# SD_Card_Multiplexer.net
KiCad netlist of a schematic drawn in Altium Designer
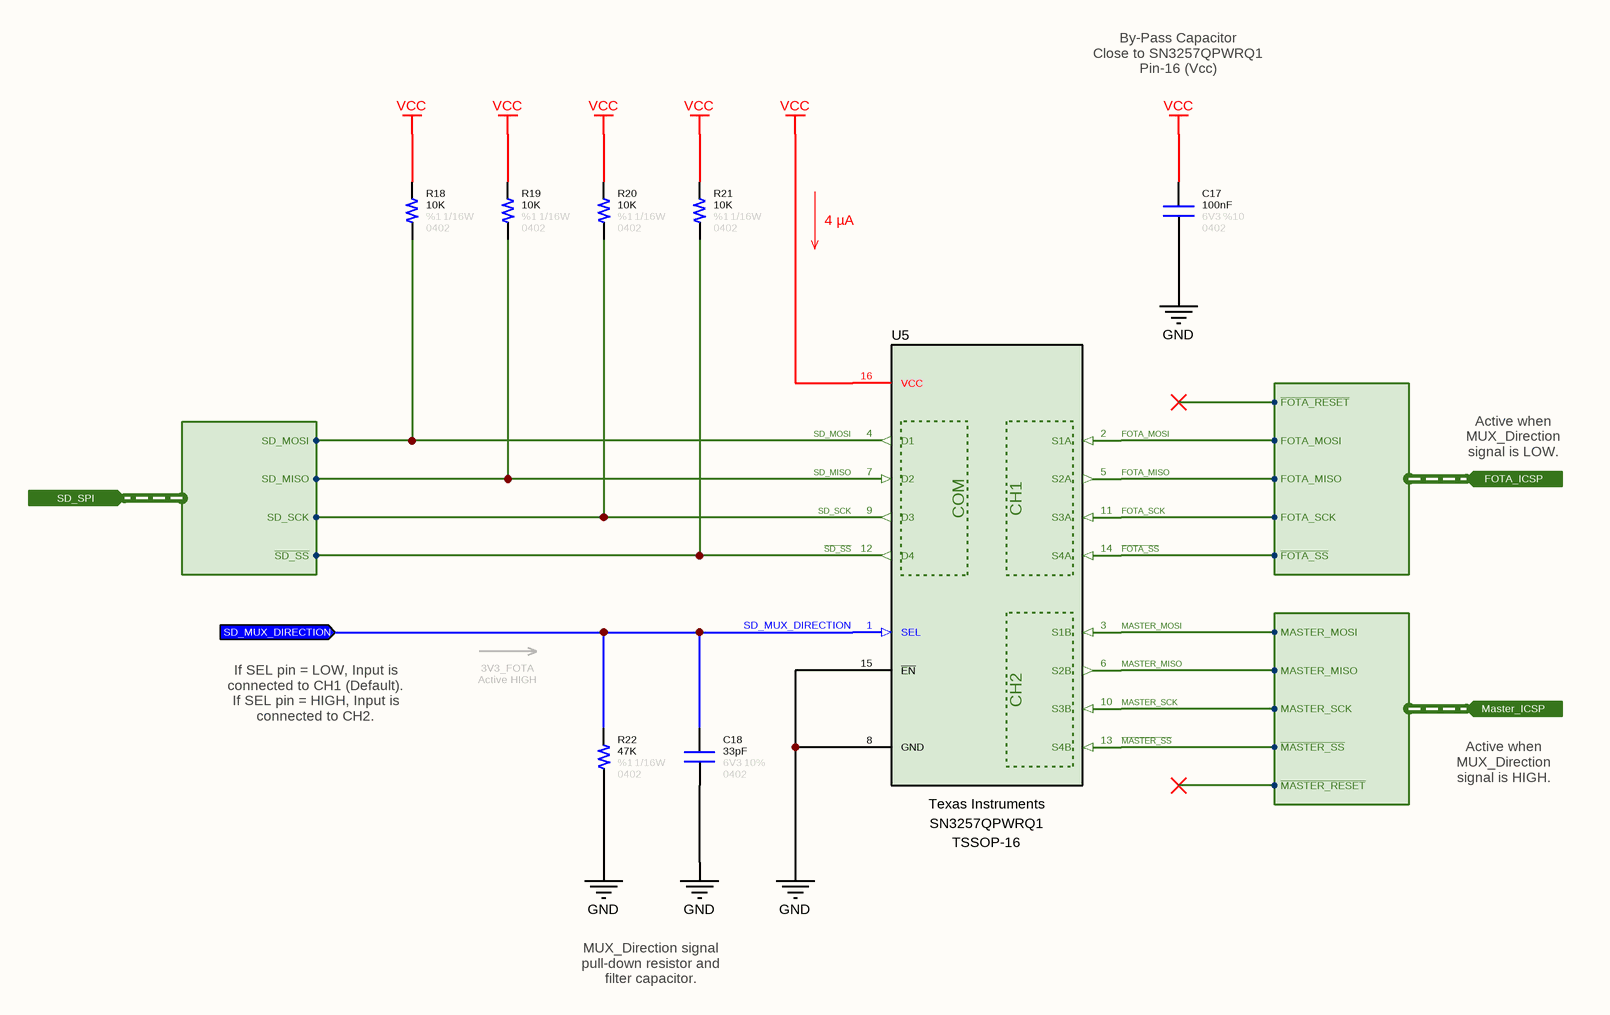
[diagram p0: SD Card Multiplexer.SchDoc]

(export (version "E")
  (design (tool "Eeschema 10.0.6"))
  (components
    (comp (ref "C17")
      (value "100nF")
      (footprint "CAPACITOR_0402")
      (description "Capacitor - 100nF [0402-6V3] (Ceramic)")
      (fields
        (field (name "MANUFACTURER PART NUMBER") "04026D104KAT4A")
        (field (name "TOLERANCE") "%10")
        (field (name "VOLTAGE") "6V3")
        (field (name "CASE") "0402")
        (field (name "Comment") "Capacitor - 100nF [0402] (Ceramic)")
      )
      (libsource (lib "P101DA_Library") (part "Capacitor - 100nF [0402-6V3]"))
    )
    (comp (ref "C18")
      (value "33pF")
      (footprint "CAPACITOR_0402")
      (description "Capacitor - 33pF [0402] (Ceramic)")
      (fields
        (field (name "MANUFACTURER PART NUMBER") "C0402C330J9RACAUTO")
        (field (name "TOLERANCE") "10%")
        (field (name "CASE") "0402")
        (field (name "VOLTAGE") "6V3")
      )
      (libsource (lib "P101DA_Library") (part "Capacitor - 33pF [0402-6V3]"))
    )
    (comp (ref "R18")
      (value "10K")
      (footprint "RESISTOR_0402")
      (description "Thick Film Resistors - SMD 1/16 W 10 KOhm 1%")
      (fields
        (field (name "MANUFACTURER PART NUMBER") "CRCW040210K0FKED")
        (field (name "TOLERANCE") "%1")
        (field (name "CASE") "0402")
        (field (name "POWER") "1/16W")
        (field (name "Comment") "10K - 0402 - %1 - 1/16W")
      )
      (libsource (lib "P101DA_Library") (part "Resistor - 10K [0402]"))
    )
    (comp (ref "R19")
      (value "10K")
      (footprint "RESISTOR_0402")
      (description "Thick Film Resistors - SMD 1/16 W 10 KOhm 1%")
      (fields
        (field (name "MANUFACTURER PART NUMBER") "CRCW040210K0FKED")
        (field (name "TOLERANCE") "%1")
        (field (name "CASE") "0402")
        (field (name "POWER") "1/16W")
        (field (name "Comment") "10K - 0402 - %1 - 1/16W")
      )
      (libsource (lib "P101DA_Library") (part "Resistor - 10K [0402]"))
    )
    (comp (ref "R20")
      (value "10K")
      (footprint "RESISTOR_0402")
      (description "Thick Film Resistors - SMD 1/16 W 10 KOhm 1%")
      (fields
        (field (name "MANUFACTURER PART NUMBER") "CRCW040210K0FKED")
        (field (name "TOLERANCE") "%1")
        (field (name "CASE") "0402")
        (field (name "POWER") "1/16W")
        (field (name "Comment") "10K - 0402 - %1 - 1/16W")
      )
      (libsource (lib "P101DA_Library") (part "Resistor - 10K [0402]"))
    )
    (comp (ref "R21")
      (value "10K")
      (footprint "RESISTOR_0402")
      (description "Thick Film Resistors - SMD 1/16 W 10 KOhm 1%")
      (fields
        (field (name "MANUFACTURER PART NUMBER") "CRCW040210K0FKED")
        (field (name "TOLERANCE") "%1")
        (field (name "CASE") "0402")
        (field (name "POWER") "1/16W")
        (field (name "Comment") "10K - 0402 - %1 - 1/16W")
      )
      (libsource (lib "P101DA_Library") (part "Resistor - 10K [0402]"))
    )
    (comp (ref "R22")
      (value "47K")
      (footprint "RESISTOR_0402")
      (description "Thick Film Resistors - SMD 1/16 W 47 KOhm 1%")
      (fields
        (field (name "MANUFACTURER PART NUMBER") "CRCW040247K0FKED")
        (field (name "TOLERANCE") "%1")
        (field (name "CASE") "0402")
        (field (name "POWER") "1/16W")
        (field (name "Comment") "47K - 0402 - %1 - 1/16W")
      )
      (libsource (lib "P101DA_Library") (part "Resistor - 47K [0402]"))
    )
    (comp (ref "U5")
      (value "SN3257QPWRQ1")
      (footprint "TSSOP-16")
      (fields
        (field (name "MANUFACTURER NAME") "Texas Instruments")
        (field (name "MANUFACTURER PART NUMBER") "SN3257QPWRQ1")
        (field (name "CASE") "TSSOP-16")
      )
      (libsource (lib "P101DA_Library") (part "IC - SN3257"))
    )
  )
  (nets
    (net (code "4") (name "/FOTA_MISO") (class "Default")
      (node (ref "U5") (pin "5") (pinfunction "S2A_5") (pintype "output"))
    )
    (net (code "5") (name "/FOTA_MOSI") (class "Default")
      (node (ref "U5") (pin "2") (pinfunction "S1A_2") (pintype "input"))
    )
    (net (code "6") (name "/FOTA_SCK") (class "Default")
      (node (ref "U5") (pin "11") (pinfunction "S3A_11") (pintype "input"))
    )
    (net (code "7") (name "/MASTER_MISO") (class "Default")
      (node (ref "U5") (pin "6") (pinfunction "S2B_6") (pintype "output"))
    )
    (net (code "8") (name "/MASTER_MOSI") (class "Default")
      (node (ref "U5") (pin "3") (pinfunction "S1B_3") (pintype "input"))
    )
    (net (code "9") (name "/MASTER_SCK") (class "Default")
      (node (ref "U5") (pin "10") (pinfunction "S3B_10") (pintype "input"))
    )
    (net (code "10") (name "/SD_MISO") (class "Default")
      (node (ref "R19") (pin "1") (pinfunction "1_1") (pintype "passive"))
      (node (ref "U5") (pin "7") (pinfunction "D2_7") (pintype "input"))
    )
    (net (code "11") (name "/SD_MOSI") (class "Default")
      (node (ref "R18") (pin "1") (pinfunction "1_1") (pintype "passive"))
      (node (ref "U5") (pin "4") (pinfunction "D1_4") (pintype "output"))
    )
    (net (code "12") (name "/SD_MUX_DIRECTION") (class "Default")
      (node (ref "C18") (pin "2") (pinfunction "2_2") (pintype "passive"))
      (node (ref "R22") (pin "2") (pinfunction "2_2") (pintype "passive"))
      (node (ref "U5") (pin "1") (pinfunction "SEL_1") (pintype "input"))
    )
    (net (code "13") (name "/SD_SCK") (class "Default")
      (node (ref "R20") (pin "1") (pinfunction "1_1") (pintype "passive"))
      (node (ref "U5") (pin "9") (pinfunction "D3_9") (pintype "output"))
    )
    (net (code "17") (name "/~{FOTA_SS}") (class "Default")
      (node (ref "U5") (pin "14") (pinfunction "S4A_14") (pintype "input"))
    )
    (net (code "18") (name "/~{MASTER_SS}") (class "Default")
      (node (ref "U5") (pin "13") (pinfunction "S4B_13") (pintype "input"))
    )
    (net (code "19") (name "/~{SD_SS}") (class "Default")
      (node (ref "R21") (pin "1") (pinfunction "1_1") (pintype "passive"))
      (node (ref "U5") (pin "12") (pinfunction "D4_12") (pintype "output"))
    )
    (net (code "20") (name "GND") (class "Default")
      (node (ref "C17") (pin "1") (pinfunction "1_1") (pintype "passive"))
      (node (ref "C18") (pin "1") (pinfunction "1_1") (pintype "passive"))
      (node (ref "R22") (pin "1") (pinfunction "1_1") (pintype "passive"))
      (node (ref "U5") (pin "15") (pinfunction "~{EN}_15") (pintype "power_in"))
      (node (ref "U5") (pin "8") (pinfunction "GND_8") (pintype "power_in"))
    )
    (net (code "21") (name "VCC") (class "Default")
      (node (ref "C17") (pin "2") (pinfunction "2_2") (pintype "passive"))
      (node (ref "R18") (pin "2") (pinfunction "2_2") (pintype "passive"))
      (node (ref "R19") (pin "2") (pinfunction "2_2") (pintype "passive"))
      (node (ref "R20") (pin "2") (pinfunction "2_2") (pintype "passive"))
      (node (ref "R21") (pin "2") (pinfunction "2_2") (pintype "passive"))
      (node (ref "U5") (pin "16") (pinfunction "VCC_16") (pintype "power_in"))
    )
  )
)
